# camera-endpoint.net
KiCad netlist of a schematic drawn in EAGLE
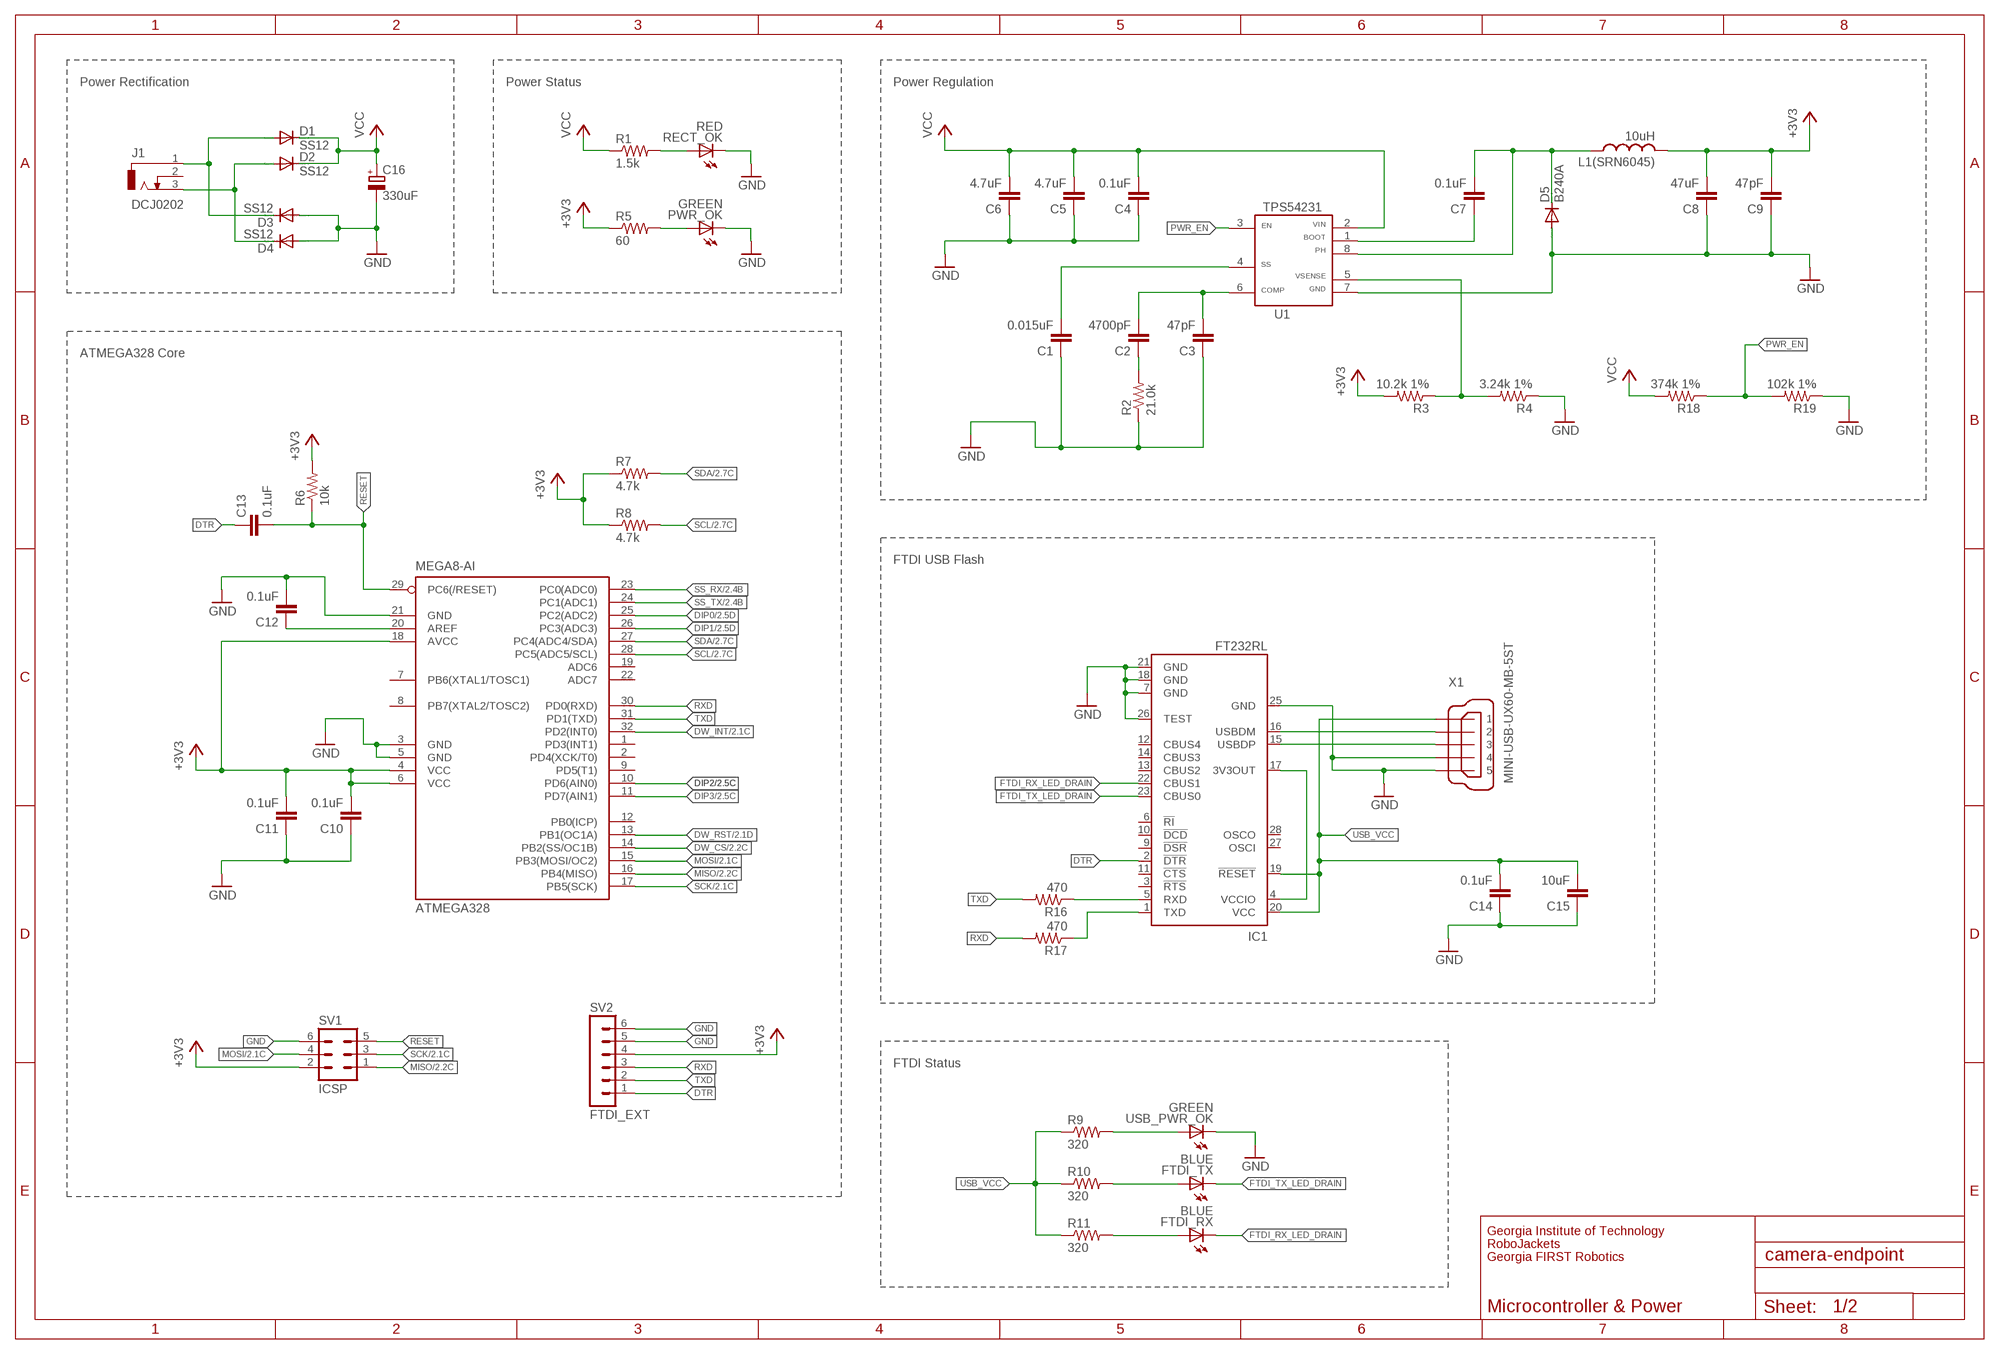
[diagram p0: schematic, sheet 1]
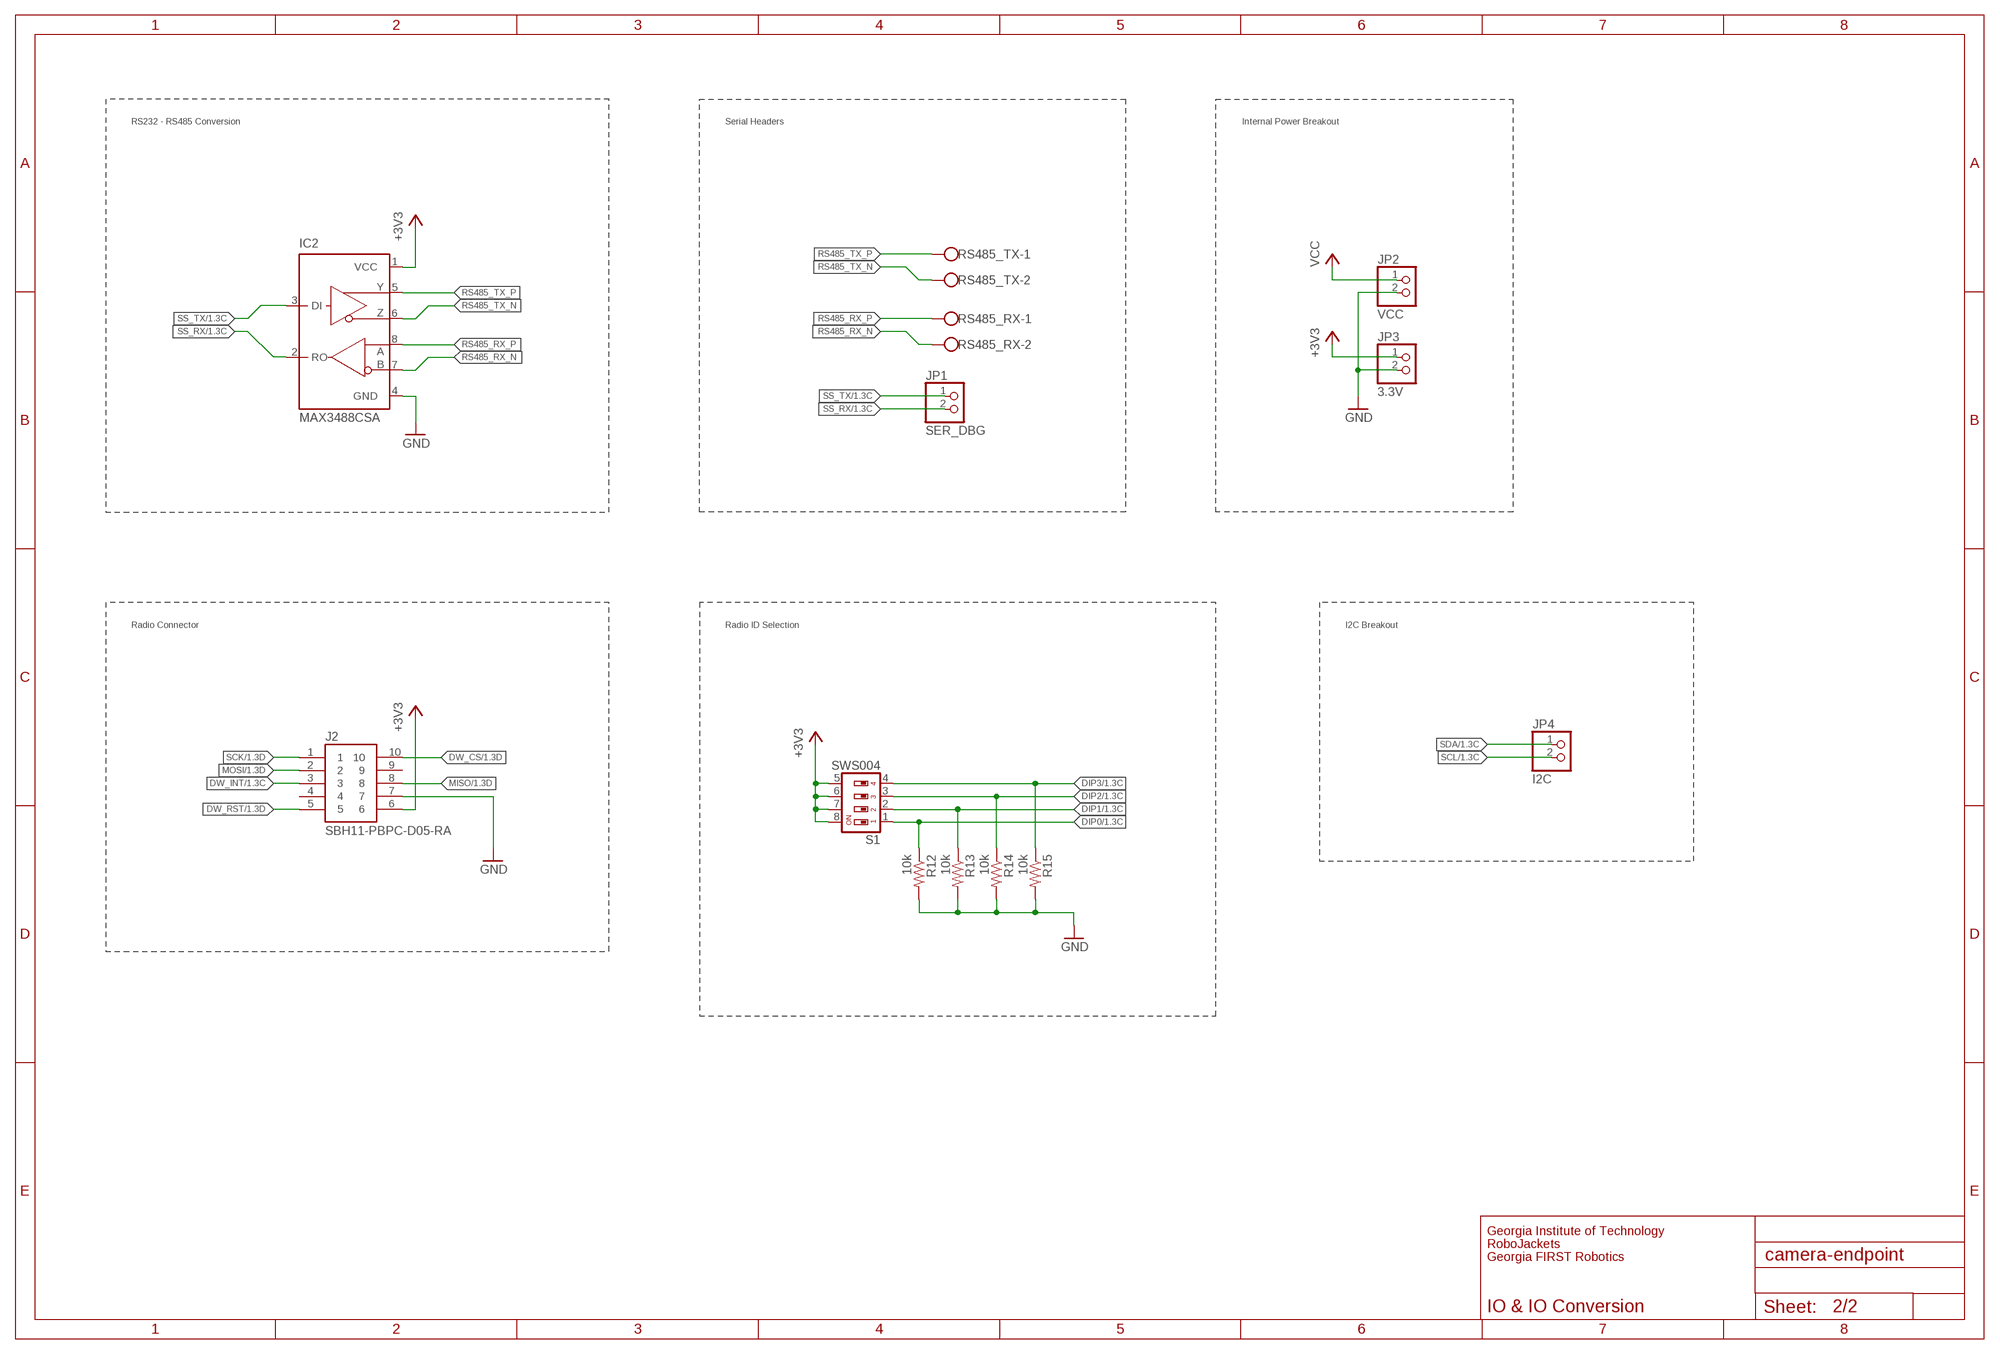
[diagram p1: schematic, sheet 2]

(export (version "E")
  (design (tool "Eeschema 10.0.6"))
  (components
    (comp (ref "IC2")
      (value "MAX3488CSA")
      (footprint "eagle-import:SO08")
      (libsource (lib "eagle-import") (part "MAX3467PAC"))
    )
    (comp (ref "J2")
      (value "SBH11-PBPC-D05-RA")
      (footprint "eagle-import:SBH11-_-D05-RA")
      (fields (field (name "MPN") "SBH11-PBPC-D05-RA-BK"))
      (libsource (lib "eagle-import") (part "SBH11--D05-?RAPBPC"))
    )
    (comp (ref "JP1")
      (value "SER_DBG")
      (footprint "eagle-import:1X02")
      (libsource (lib "eagle-import") (part "PINHD-1X2"))
    )
    (comp (ref "JP2")
      (value "VCC")
      (footprint "eagle-import:1X02")
      (libsource (lib "eagle-import") (part "PINHD-1X2"))
    )
    (comp (ref "JP3")
      (value "3.3V")
      (footprint "eagle-import:1X02")
      (libsource (lib "eagle-import") (part "PINHD-1X2"))
    )
    (comp (ref "JP4")
      (value "I2C")
      (footprint "eagle-import:1X02")
      (libsource (lib "eagle-import") (part "PINHD-1X2"))
    )
    (comp (ref "R12")
      (value "10k")
      (footprint "eagle-import:R0603")
      (libsource (lib "eagle-import") (part "R-US_R0603"))
    )
    (comp (ref "R13")
      (value "10k")
      (footprint "eagle-import:R0603")
      (libsource (lib "eagle-import") (part "R-US_R0603"))
    )
    (comp (ref "R14")
      (value "10k")
      (footprint "eagle-import:R0603")
      (libsource (lib "eagle-import") (part "R-US_R0603"))
    )
    (comp (ref "R15")
      (value "10k")
      (footprint "eagle-import:R0603")
      (libsource (lib "eagle-import") (part "R-US_R0603"))
    )
    (comp (ref "RS485_RX")
      (value "W237-102")
      (footprint "eagle-import:W237-102")
      (fields (field (name "MPN") "237-102"))
      (libsource (lib "eagle-import") (part "W237-102"))
    )
    (comp (ref "RS485_TX")
      (value "W237-102")
      (footprint "eagle-import:W237-102")
      (fields (field (name "MPN") "237-102"))
      (libsource (lib "eagle-import") (part "W237-102"))
    )
    (comp (ref "S1")
      (value "SWS004")
      (footprint "eagle-import:SMS-004")
      (libsource (lib "eagle-import") (part "SWS004"))
    )
    (comp (ref "ATMEGA328")
      (value "MEGA8-AI")
      (footprint "eagle-import:TQFP32-08")
      (fields (field (name "MPN") "ATMEGA8-16AU"))
      (libsource (lib "eagle-import") (part "MEGA8-AI"))
    )
    (comp (ref "C1")
      (value "0.015uF")
      (footprint "eagle-import:C0603")
      (libsource (lib "eagle-import") (part "resistor_348_C-EUC0603"))
    )
    (comp (ref "C2")
      (value "4700pF")
      (footprint "eagle-import:C0603")
      (libsource (lib "eagle-import") (part "resistor_348_C-EUC0603"))
    )
    (comp (ref "C3")
      (value "47pF")
      (footprint "eagle-import:C0603")
      (libsource (lib "eagle-import") (part "resistor_348_C-EUC0603"))
    )
    (comp (ref "C4")
      (value "0.1uF")
      (footprint "eagle-import:C0603")
      (libsource (lib "eagle-import") (part "resistor_348_C-EUC0603"))
    )
    (comp (ref "C5")
      (value "4.7uF")
      (footprint "eagle-import:C0603")
      (libsource (lib "eagle-import") (part "resistor_348_C-EUC0603"))
    )
    (comp (ref "C6")
      (value "4.7uF")
      (footprint "eagle-import:C0603")
      (libsource (lib "eagle-import") (part "resistor_348_C-EUC0603"))
    )
    (comp (ref "C7")
      (value "0.1uF")
      (footprint "eagle-import:C0603")
      (libsource (lib "eagle-import") (part "resistor_348_C-EUC0603"))
    )
    (comp (ref "C8")
      (value "47uF")
      (footprint "eagle-import:C1206")
      (libsource (lib "eagle-import") (part "C-EUC1206"))
    )
    (comp (ref "C9")
      (value "47pF")
      (footprint "eagle-import:C0603")
      (libsource (lib "eagle-import") (part "resistor_348_C-EUC0603"))
    )
    (comp (ref "C10")
      (value "0.1uF")
      (footprint "eagle-import:C0603")
      (libsource (lib "eagle-import") (part "resistor_348_C-EUC0603"))
    )
    (comp (ref "C11")
      (value "0.1uF")
      (footprint "eagle-import:C0603")
      (libsource (lib "eagle-import") (part "resistor_348_C-EUC0603"))
    )
    (comp (ref "C12")
      (value "0.1uF")
      (footprint "eagle-import:C0603")
      (libsource (lib "eagle-import") (part "resistor_348_C-EUC0603"))
    )
    (comp (ref "C13")
      (value "0.1uF")
      (footprint "eagle-import:C0603")
      (libsource (lib "eagle-import") (part "resistor_348_C-EUC0603"))
    )
    (comp (ref "C14")
      (value "0.1uF")
      (footprint "eagle-import:C0603")
      (libsource (lib "eagle-import") (part "resistor_348_C-EUC0603"))
    )
    (comp (ref "C15")
      (value "10uF")
      (footprint "eagle-import:C0603")
      (libsource (lib "eagle-import") (part "resistor_348_C-EUC0603"))
    )
    (comp (ref "C16")
      (value "330uF")
      (footprint "eagle-import:E5-8,5")
      (libsource (lib "eagle-import") (part "CPOL-EUE5-8.5"))
    )
    (comp (ref "D1")
      (value "SS12")
      (footprint "eagle-import:DO214AC")
      (libsource (lib "eagle-import") (part "DIODE-DO214AC"))
    )
    (comp (ref "D2")
      (value "SS12")
      (footprint "eagle-import:DO214AC")
      (libsource (lib "eagle-import") (part "DIODE-DO214AC"))
    )
    (comp (ref "D3")
      (value "SS12")
      (footprint "eagle-import:DO214AC")
      (libsource (lib "eagle-import") (part "DIODE-DO214AC"))
    )
    (comp (ref "D4")
      (value "SS12")
      (footprint "eagle-import:DO214AC")
      (libsource (lib "eagle-import") (part "DIODE-DO214AC"))
    )
    (comp (ref "D5")
      (value "B240A")
      (footprint "eagle-import:DO-214AC")
      (libsource (lib "eagle-import") (part "DIODE-DO-214AC"))
    )
    (comp (ref "FTDI_RX")
      (value "BLUE")
      (footprint "eagle-import:CHIP-LED0603")
      (libsource (lib "eagle-import") (part "LEDCHIP-LED0603"))
    )
    (comp (ref "FTDI_TX")
      (value "BLUE")
      (footprint "eagle-import:CHIP-LED0603")
      (libsource (lib "eagle-import") (part "LEDCHIP-LED0603"))
    )
    (comp (ref "IC1")
      (value "FT232RL")
      (footprint "eagle-import:SSOP28")
      (libsource (lib "eagle-import") (part "FT232RL"))
    )
    (comp (ref "J1")
      (value "DCJ0202")
      (footprint "eagle-import:DCJ0202")
      (libsource (lib "eagle-import") (part "DCJ0202"))
    )
    (comp (ref "L1(SRN6045)")
      (value "10uH")
      (footprint "eagle-import:POWER-CHOKE_WE-TPC")
      (libsource (lib "eagle-import") (part "L-USWE-TPC"))
    )
    (comp (ref "PWR_OK")
      (value "GREEN")
      (footprint "eagle-import:LED5MM")
      (libsource (lib "eagle-import") (part "LED5MM"))
    )
    (comp (ref "R1")
      (value "1.5k")
      (footprint "eagle-import:R0603")
      (libsource (lib "eagle-import") (part "R-US_R0603"))
    )
    (comp (ref "R2")
      (value "21.0k")
      (footprint "eagle-import:R0603")
      (libsource (lib "eagle-import") (part "R-US_R0603"))
    )
    (comp (ref "R3")
      (value "10.2k 1%")
      (footprint "eagle-import:R0603")
      (libsource (lib "eagle-import") (part "R-US_R0603"))
    )
    (comp (ref "R4")
      (value "3.24k 1%")
      (footprint "eagle-import:R0603")
      (libsource (lib "eagle-import") (part "R-US_R0603"))
    )
    (comp (ref "R5")
      (value "60")
      (footprint "eagle-import:R0603")
      (libsource (lib "eagle-import") (part "R-US_R0603"))
    )
    (comp (ref "R6")
      (value "10k")
      (footprint "eagle-import:R0603")
      (libsource (lib "eagle-import") (part "R-US_R0603"))
    )
    (comp (ref "R7")
      (value "4.7k")
      (footprint "eagle-import:R0603")
      (libsource (lib "eagle-import") (part "R-US_R0603"))
    )
    (comp (ref "R8")
      (value "4.7k")
      (footprint "eagle-import:R0603")
      (libsource (lib "eagle-import") (part "R-US_R0603"))
    )
    (comp (ref "R9")
      (value "320")
      (footprint "eagle-import:R0603")
      (libsource (lib "eagle-import") (part "R-US_R0603"))
    )
    (comp (ref "R10")
      (value "320")
      (footprint "eagle-import:R0603")
      (libsource (lib "eagle-import") (part "R-US_R0603"))
    )
    (comp (ref "R11")
      (value "320")
      (footprint "eagle-import:R0603")
      (libsource (lib "eagle-import") (part "R-US_R0603"))
    )
    (comp (ref "R16")
      (value "470")
      (footprint "eagle-import:R0603")
      (libsource (lib "eagle-import") (part "R-US_R0603"))
    )
    (comp (ref "R17")
      (value "470")
      (footprint "eagle-import:R0603")
      (libsource (lib "eagle-import") (part "R-US_R0603"))
    )
    (comp (ref "R18")
      (value "374k 1%")
      (footprint "eagle-import:R0603")
      (libsource (lib "eagle-import") (part "R-US_R0603"))
    )
    (comp (ref "R19")
      (value "102k 1%")
      (footprint "eagle-import:R0603")
      (libsource (lib "eagle-import") (part "R-US_R0603"))
    )
    (comp (ref "RECT_OK")
      (value "RED")
      (footprint "eagle-import:LED5MM")
      (libsource (lib "eagle-import") (part "LED5MM"))
    )
    (comp (ref "SV1")
      (value "ICSP")
      (footprint "eagle-import:MA03-2")
      (libsource (lib "eagle-import") (part "MA03-2"))
    )
    (comp (ref "SV2")
      (value "FTDI_EXT")
      (footprint "eagle-import:MA06-1")
      (libsource (lib "eagle-import") (part "MA06-1"))
    )
    (comp (ref "U1")
      (value "TPS54231SO8")
      (footprint "eagle-import:SO8")
      (libsource (lib "eagle-import") (part "TPS54231SO8"))
    )
    (comp (ref "USB_PWR_OK")
      (value "GREEN")
      (footprint "eagle-import:CHIP-LED0603")
      (libsource (lib "eagle-import") (part "LEDCHIP-LED0603"))
    )
    (comp (ref "X1")
      (value "MINI-USB-UX60-MB-5ST")
      (footprint "eagle-import:UX60-MB-5ST")
      (libsource (lib "eagle-import") (part "MINI-USB-UX60-MB-5ST"))
    )
  )
  (nets
    (net (code "1") (name "+3V3") (class "Default")
      (node (ref "ATMEGA328") (pin "18") (pinfunction "AVCC_18") (pintype "power_in"))
      (node (ref "ATMEGA328") (pin "4") (pinfunction "VCC_4") (pintype "power_in"))
      (node (ref "ATMEGA328") (pin "6") (pinfunction "VCC_6") (pintype "power_in"))
      (node (ref "C10") (pin "2") (pinfunction "2_2") (pintype "passive"))
      (node (ref "C11") (pin "2") (pinfunction "2_2") (pintype "passive"))
      (node (ref "C8") (pin "2") (pinfunction "2_2") (pintype "passive"))
      (node (ref "C9") (pin "2") (pinfunction "2_2") (pintype "passive"))
      (node (ref "IC2") (pin "1") (pinfunction "VCC_1") (pintype "power_in"))
      (node (ref "J2") (pin "6") (pinfunction "6_6") (pintype "bidirectional"))
      (node (ref "JP3") (pin "1") (pinfunction "1_1") (pintype "passive"))
      (node (ref "L1(SRN6045)") (pin "2") (pinfunction "2_2") (pintype "passive"))
      (node (ref "R3") (pin "2") (pinfunction "2_2") (pintype "passive"))
      (node (ref "R5") (pin "1") (pinfunction "1_1") (pintype "passive"))
      (node (ref "R6") (pin "2") (pinfunction "2_2") (pintype "passive"))
      (node (ref "R7") (pin "1") (pinfunction "1_1") (pintype "passive"))
      (node (ref "R8") (pin "1") (pinfunction "1_1") (pintype "passive"))
      (node (ref "S1") (pin "5") (pinfunction "5_5") (pintype "passive"))
      (node (ref "S1") (pin "6") (pinfunction "6_6") (pintype "passive"))
      (node (ref "S1") (pin "7") (pinfunction "7_7") (pintype "passive"))
      (node (ref "S1") (pin "8") (pinfunction "8_8") (pintype "passive"))
      (node (ref "SV1") (pin "2") (pinfunction "2_2") (pintype "passive"))
      (node (ref "SV2") (pin "4") (pinfunction "4_4") (pintype "passive"))
    )
    (net (code "2") (name "DIP0") (class "Default")
      (node (ref "ATMEGA328") (pin "25") (pinfunction "PC2(ADC2)_25") (pintype "bidirectional"))
      (node (ref "R12") (pin "1") (pinfunction "1_1") (pintype "passive"))
      (node (ref "S1") (pin "1") (pinfunction "1_1") (pintype "passive"))
    )
    (net (code "3") (name "DIP1") (class "Default")
      (node (ref "ATMEGA328") (pin "26") (pinfunction "PC3(ADC3)_26") (pintype "bidirectional"))
      (node (ref "R13") (pin "1") (pinfunction "1_1") (pintype "passive"))
      (node (ref "S1") (pin "2") (pinfunction "2_2") (pintype "passive"))
    )
    (net (code "4") (name "DIP2") (class "Default")
      (node (ref "ATMEGA328") (pin "10") (pinfunction "PD6(AIN0)_10") (pintype "bidirectional"))
      (node (ref "R14") (pin "1") (pinfunction "1_1") (pintype "passive"))
      (node (ref "S1") (pin "3") (pinfunction "3_3") (pintype "passive"))
    )
    (net (code "5") (name "DIP3") (class "Default")
      (node (ref "ATMEGA328") (pin "11") (pinfunction "PD7(AIN1)_11") (pintype "bidirectional"))
      (node (ref "R15") (pin "1") (pinfunction "1_1") (pintype "passive"))
      (node (ref "S1") (pin "4") (pinfunction "4_4") (pintype "passive"))
    )
    (net (code "6") (name "DTR") (class "Default")
      (node (ref "C13") (pin "1") (pinfunction "1_1") (pintype "passive"))
      (node (ref "IC1") (pin "2") (pinfunction "~{DTR}_2") (pintype "output"))
      (node (ref "SV2") (pin "1") (pinfunction "1_1") (pintype "passive"))
    )
    (net (code "7") (name "DW_CS") (class "Default")
      (node (ref "ATMEGA328") (pin "14") (pinfunction "PB2(SS/OC1B)_14") (pintype "bidirectional"))
      (node (ref "J2") (pin "10") (pinfunction "10_10") (pintype "bidirectional"))
    )
    (net (code "8") (name "DW_INT") (class "Default")
      (node (ref "ATMEGA328") (pin "32") (pinfunction "PD2(INT0)_32") (pintype "bidirectional"))
      (node (ref "J2") (pin "3") (pinfunction "3_3") (pintype "bidirectional"))
    )
    (net (code "9") (name "DW_RST") (class "Default")
      (node (ref "ATMEGA328") (pin "13") (pinfunction "PB1(OC1A)_13") (pintype "bidirectional"))
      (node (ref "J2") (pin "5") (pinfunction "5_5") (pintype "bidirectional"))
    )
    (net (code "10") (name "FTDI_RX_LED_DRAIN") (class "Default")
      (node (ref "FTDI_RX") (pin "C") (pinfunction "C_C") (pintype "passive"))
      (node (ref "IC1") (pin "22") (pinfunction "CBUS1_22") (pintype "bidirectional"))
    )
    (net (code "11") (name "FTDI_TX_LED_DRAIN") (class "Default")
      (node (ref "FTDI_TX") (pin "C") (pinfunction "C_C") (pintype "passive"))
      (node (ref "IC1") (pin "23") (pinfunction "CBUS0_23") (pintype "bidirectional"))
    )
    (net (code "12") (name "GND") (class "Default")
      (node (ref "ATMEGA328") (pin "21") (pinfunction "GND_21") (pintype "power_in"))
      (node (ref "ATMEGA328") (pin "3") (pinfunction "GND_3") (pintype "power_in"))
      (node (ref "ATMEGA328") (pin "5") (pinfunction "GND_5") (pintype "power_in"))
      (node (ref "C1") (pin "1") (pinfunction "1_1") (pintype "passive"))
      (node (ref "C10") (pin "1") (pinfunction "1_1") (pintype "passive"))
      (node (ref "C11") (pin "1") (pinfunction "1_1") (pintype "passive"))
      (node (ref "C12") (pin "2") (pinfunction "2_2") (pintype "passive"))
      (node (ref "C14") (pin "1") (pinfunction "1_1") (pintype "passive"))
      (node (ref "C15") (pin "1") (pinfunction "1_1") (pintype "passive"))
      (node (ref "C16") (pin "-") (pinfunction "-_-") (pintype "passive"))
      (node (ref "C3") (pin "1") (pinfunction "1_1") (pintype "passive"))
      (node (ref "C4") (pin "1") (pinfunction "1_1") (pintype "passive"))
      (node (ref "C5") (pin "1") (pinfunction "1_1") (pintype "passive"))
      (node (ref "C6") (pin "1") (pinfunction "1_1") (pintype "passive"))
      (node (ref "C8") (pin "1") (pinfunction "1_1") (pintype "passive"))
      (node (ref "C9") (pin "1") (pinfunction "1_1") (pintype "passive"))
      (node (ref "D3") (pin "A") (pinfunction "A_A") (pintype "passive"))
      (node (ref "D4") (pin "A") (pinfunction "A_A") (pintype "passive"))
      (node (ref "D5") (pin "A") (pinfunction "A_A") (pintype "passive"))
      (node (ref "IC1") (pin "18") (pinfunction "GND_18") (pintype "power_in"))
      (node (ref "IC1") (pin "21") (pinfunction "GND_21") (pintype "power_in"))
      (node (ref "IC1") (pin "25") (pinfunction "GND_25") (pintype "power_in"))
      (node (ref "IC1") (pin "26") (pinfunction "TEST_26") (pintype "input"))
      (node (ref "IC1") (pin "7") (pinfunction "GND_7") (pintype "power_in"))
      (node (ref "IC2") (pin "4") (pinfunction "GND_4") (pintype "power_in"))
      (node (ref "J2") (pin "7") (pinfunction "7_7") (pintype "bidirectional"))
      (node (ref "JP2") (pin "2") (pinfunction "2_2") (pintype "passive"))
      (node (ref "JP3") (pin "2") (pinfunction "2_2") (pintype "passive"))
      (node (ref "PWR_OK") (pin "K") (pinfunction "C_K") (pintype "passive"))
      (node (ref "R12") (pin "2") (pinfunction "2_2") (pintype "passive"))
      (node (ref "R13") (pin "2") (pinfunction "2_2") (pintype "passive"))
      (node (ref "R14") (pin "2") (pinfunction "2_2") (pintype "passive"))
      (node (ref "R15") (pin "2") (pinfunction "2_2") (pintype "passive"))
      (node (ref "R19") (pin "1") (pinfunction "1_1") (pintype "passive"))
      (node (ref "R2") (pin "1") (pinfunction "1_1") (pintype "passive"))
      (node (ref "R4") (pin "1") (pinfunction "1_1") (pintype "passive"))
      (node (ref "RECT_OK") (pin "K") (pinfunction "C_K") (pintype "passive"))
      (node (ref "SV1") (pin "6") (pinfunction "6_6") (pintype "passive"))
      (node (ref "SV2") (pin "5") (pinfunction "5_5") (pintype "passive"))
      (node (ref "SV2") (pin "6") (pinfunction "6_6") (pintype "passive"))
      (node (ref "U1") (pin "7") (pinfunction "7_7") (pintype "bidirectional"))
      (node (ref "USB_PWR_OK") (pin "C") (pinfunction "C_C") (pintype "passive"))
      (node (ref "X1") (pin "4") (pinfunction "4_4") (pintype "input"))
      (node (ref "X1") (pin "5") (pinfunction "5_5") (pintype "input"))
    )
    (net (code "13") (name "MISO") (class "Default")
      (node (ref "ATMEGA328") (pin "16") (pinfunction "PB4(MISO)_16") (pintype "bidirectional"))
      (node (ref "J2") (pin "8") (pinfunction "8_8") (pintype "bidirectional"))
      (node (ref "SV1") (pin "1") (pinfunction "1_1") (pintype "passive"))
    )
    (net (code "14") (name "MOSI") (class "Default")
      (node (ref "ATMEGA328") (pin "15") (pinfunction "PB3(MOSI/OC2)_15") (pintype "bidirectional"))
      (node (ref "J2") (pin "2") (pinfunction "2_2") (pintype "bidirectional"))
      (node (ref "SV1") (pin "4") (pinfunction "4_4") (pintype "passive"))
    )
    (net (code "15") (name "Net-(ATMEGA328-AREF)") (class "Default")
      (node (ref "ATMEGA328") (pin "20") (pinfunction "AREF_20") (pintype "passive"))
      (node (ref "C12") (pin "1") (pinfunction "1_1") (pintype "passive"))
    )
    (net (code "16") (name "Net-(C1-Pad2)") (class "Default")
      (node (ref "C1") (pin "2") (pinfunction "2_2") (pintype "passive"))
      (node (ref "U1") (pin "4") (pinfunction "4_4") (pintype "bidirectional"))
    )
    (net (code "17") (name "Net-(C2-Pad1)") (class "Default")
      (node (ref "C2") (pin "1") (pinfunction "1_1") (pintype "passive"))
      (node (ref "R2") (pin "2") (pinfunction "2_2") (pintype "passive"))
    )
    (net (code "18") (name "Net-(C2-Pad2)") (class "Default")
      (node (ref "C2") (pin "2") (pinfunction "2_2") (pintype "passive"))
      (node (ref "C3") (pin "2") (pinfunction "2_2") (pintype "passive"))
      (node (ref "U1") (pin "6") (pinfunction "6_6") (pintype "bidirectional"))
    )
    (net (code "19") (name "Net-(C7-Pad1)") (class "Default")
      (node (ref "C7") (pin "1") (pinfunction "1_1") (pintype "passive"))
      (node (ref "U1") (pin "1") (pinfunction "1_1") (pintype "bidirectional"))
    )
    (net (code "20") (name "Net-(C7-Pad2)") (class "Default")
      (node (ref "C7") (pin "2") (pinfunction "2_2") (pintype "passive"))
      (node (ref "D5") (pin "C") (pinfunction "C_C") (pintype "passive"))
      (node (ref "L1(SRN6045)") (pin "1") (pinfunction "1_1") (pintype "passive"))
      (node (ref "U1") (pin "8") (pinfunction "8_8") (pintype "bidirectional"))
    )
    (net (code "21") (name "Net-(D1-PadA)") (class "Default")
      (node (ref "D1") (pin "A") (pinfunction "A_A") (pintype "passive"))
      (node (ref "D3") (pin "C") (pinfunction "C_C") (pintype "passive"))
      (node (ref "J1") (pin "1") (pinfunction "1_1") (pintype "passive"))
    )
    (net (code "22") (name "Net-(D2-PadA)") (class "Default")
      (node (ref "D2") (pin "A") (pinfunction "A_A") (pintype "passive"))
      (node (ref "D4") (pin "C") (pinfunction "C_C") (pintype "passive"))
      (node (ref "J1") (pin "3") (pinfunction "3_3") (pintype "passive"))
    )
    (net (code "23") (name "Net-(FTDI_RX-PadA)") (class "Default")
      (node (ref "FTDI_RX") (pin "A") (pinfunction "A_A") (pintype "passive"))
      (node (ref "R11") (pin "2") (pinfunction "2_2") (pintype "passive"))
    )
    (net (code "24") (name "Net-(FTDI_TX-PadA)") (class "Default")
      (node (ref "FTDI_TX") (pin "A") (pinfunction "A_A") (pintype "passive"))
      (node (ref "R10") (pin "2") (pinfunction "2_2") (pintype "passive"))
    )
    (net (code "25") (name "Net-(IC1-3V3OUT)") (class "Default")
      (node (ref "IC1") (pin "17") (pinfunction "3V3OUT_17") (pintype "output"))
      (node (ref "IC1") (pin "4") (pinfunction "VCCIO_4") (pintype "power_in"))
    )
    (net (code "26") (name "Net-(IC1-RXD)") (class "Default")
      (node (ref "IC1") (pin "5") (pinfunction "RXD_5") (pintype "input"))
      (node (ref "R16") (pin "1") (pinfunction "1_1") (pintype "passive"))
    )
    (net (code "27") (name "Net-(IC1-TXD)") (class "Default")
      (node (ref "IC1") (pin "1") (pinfunction "TXD_1") (pintype "output"))
      (node (ref "R17") (pin "1") (pinfunction "1_1") (pintype "passive"))
    )
    (net (code "28") (name "Net-(IC1-USBDM)") (class "Default")
      (node (ref "IC1") (pin "16") (pinfunction "USBDM_16") (pintype "bidirectional"))
      (node (ref "X1") (pin "2") (pinfunction "2_2") (pintype "input"))
    )
    (net (code "29") (name "Net-(IC1-USBDP)") (class "Default")
      (node (ref "IC1") (pin "15") (pinfunction "USBDP_15") (pintype "bidirectional"))
      (node (ref "X1") (pin "3") (pinfunction "3_3") (pintype "input"))
    )
    (net (code "30") (name "Net-(PWR_OK-PadA)") (class "Default")
      (node (ref "PWR_OK") (pin "A") (pinfunction "A_A") (pintype "passive"))
      (node (ref "R5") (pin "2") (pinfunction "2_2") (pintype "passive"))
    )
    (net (code "31") (name "Net-(R1-Pad2)") (class "Default")
      (node (ref "R1") (pin "2") (pinfunction "2_2") (pintype "passive"))
      (node (ref "RECT_OK") (pin "A") (pinfunction "A_A") (pintype "passive"))
    )
    (net (code "32") (name "Net-(R3-Pad1)") (class "Default")
      (node (ref "R3") (pin "1") (pinfunction "1_1") (pintype "passive"))
      (node (ref "R4") (pin "2") (pinfunction "2_2") (pintype "passive"))
      (node (ref "U1") (pin "5") (pinfunction "5_5") (pintype "bidirectional"))
    )
    (net (code "33") (name "Net-(R9-Pad2)") (class "Default")
      (node (ref "R9") (pin "2") (pinfunction "2_2") (pintype "passive"))
      (node (ref "USB_PWR_OK") (pin "A") (pinfunction "A_A") (pintype "passive"))
    )
    (net (code "34") (name "PWR_EN") (class "Default")
      (node (ref "R18") (pin "1") (pinfunction "1_1") (pintype "passive"))
      (node (ref "R19") (pin "2") (pinfunction "2_2") (pintype "passive"))
      (node (ref "U1") (pin "3") (pinfunction "3_3") (pintype "bidirectional"))
    )
    (net (code "35") (name "RESET") (class "Default")
      (node (ref "ATMEGA328") (pin "29") (pinfunction "PC6(/RESET)_29") (pintype "bidirectional"))
      (node (ref "C13") (pin "2") (pinfunction "2_2") (pintype "passive"))
      (node (ref "R6") (pin "1") (pinfunction "1_1") (pintype "passive"))
      (node (ref "SV1") (pin "5") (pinfunction "5_5") (pintype "passive"))
    )
    (net (code "36") (name "RS485_RX_N") (class "Default")
      (node (ref "IC2") (pin "7") (pinfunction "B_7") (pintype "passive"))
      (node (ref "RS485_RX") (pin "2") (pinfunction "KL_2") (pintype "passive"))
    )
    (net (code "37") (name "RS485_RX_P") (class "Default")
      (node (ref "IC2") (pin "8") (pinfunction "A_8") (pintype "passive"))
      (node (ref "RS485_RX") (pin "1") (pinfunction "KL_1") (pintype "passive"))
    )
    (net (code "38") (name "RS485_TX_N") (class "Default")
      (node (ref "IC2") (pin "6") (pinfunction "Z_6") (pintype "passive"))
      (node (ref "RS485_TX") (pin "2") (pinfunction "KL_2") (pintype "passive"))
    )
    (net (code "39") (name "RS485_TX_P") (class "Default")
      (node (ref "IC2") (pin "5") (pinfunction "Y_5") (pintype "passive"))
      (node (ref "RS485_TX") (pin "1") (pinfunction "KL_1") (pintype "passive"))
    )
    (net (code "40") (name "RXD") (class "Default")
      (node (ref "ATMEGA328") (pin "30") (pinfunction "PD0(RXD)_30") (pintype "bidirectional"))
      (node (ref "R17") (pin "2") (pinfunction "2_2") (pintype "passive"))
      (node (ref "SV2") (pin "3") (pinfunction "3_3") (pintype "passive"))
    )
    (net (code "41") (name "SCK") (class "Default")
      (node (ref "ATMEGA328") (pin "17") (pinfunction "PB5(SCK)_17") (pintype "bidirectional"))
      (node (ref "J2") (pin "1") (pinfunction "1_1") (pintype "bidirectional"))
      (node (ref "SV1") (pin "3") (pinfunction "3_3") (pintype "passive"))
    )
    (net (code "42") (name "SCL") (class "Default")
      (node (ref "ATMEGA328") (pin "28") (pinfunction "PC5(ADC5/SCL)_28") (pintype "bidirectional"))
      (node (ref "JP4") (pin "2") (pinfunction "2_2") (pintype "passive"))
      (node (ref "R8") (pin "2") (pinfunction "2_2") (pintype "passive"))
    )
    (net (code "43") (name "SDA") (class "Default")
      (node (ref "ATMEGA328") (pin "27") (pinfunction "PC4(ADC4/SDA)_27") (pintype "bidirectional"))
      (node (ref "JP4") (pin "1") (pinfunction "1_1") (pintype "passive"))
      (node (ref "R7") (pin "2") (pinfunction "2_2") (pintype "passive"))
    )
    (net (code "44") (name "SS_RX") (class "Default")
      (node (ref "ATMEGA328") (pin "23") (pinfunction "PC0(ADC0)_23") (pintype "bidirectional"))
      (node (ref "IC2") (pin "2") (pinfunction "RO_2") (pintype "output"))
      (node (ref "JP1") (pin "2") (pinfunction "2_2") (pintype "passive"))
    )
    (net (code "45") (name "SS_TX") (class "Default")
      (node (ref "ATMEGA328") (pin "24") (pinfunction "PC1(ADC1)_24") (pintype "bidirectional"))
      (node (ref "IC2") (pin "3") (pinfunction "DI_3") (pintype "input"))
      (node (ref "JP1") (pin "1") (pinfunction "1_1") (pintype "passive"))
    )
    (net (code "46") (name "TXD") (class "Default")
      (node (ref "ATMEGA328") (pin "31") (pinfunction "PD1(TXD)_31") (pintype "bidirectional"))
      (node (ref "R16") (pin "2") (pinfunction "2_2") (pintype "passive"))
      (node (ref "SV2") (pin "2") (pinfunction "2_2") (pintype "passive"))
    )
    (net (code "47") (name "USB_VCC") (class "Default")
      (node (ref "C14") (pin "2") (pinfunction "2_2") (pintype "passive"))
      (node (ref "C15") (pin "2") (pinfunction "2_2") (pintype "passive"))
      (node (ref "IC1") (pin "19") (pinfunction "~{RESET}_19") (pintype "input"))
      (node (ref "IC1") (pin "20") (pinfunction "VCC_20") (pintype "power_in"))
      (node (ref "R10") (pin "1") (pinfunction "1_1") (pintype "passive"))
      (node (ref "R11") (pin "1") (pinfunction "1_1") (pintype "passive"))
      (node (ref "R9") (pin "1") (pinfunction "1_1") (pintype "passive"))
      (node (ref "X1") (pin "1") (pinfunction "1_1") (pintype "input"))
    )
    (net (code "48") (name "VCC") (class "Default")
      (node (ref "C16") (pin "+") (pinfunction "+_+") (pintype "passive"))
      (node (ref "C4") (pin "2") (pinfunction "2_2") (pintype "passive"))
      (node (ref "C5") (pin "2") (pinfunction "2_2") (pintype "passive"))
      (node (ref "C6") (pin "2") (pinfunction "2_2") (pintype "passive"))
      (node (ref "D1") (pin "C") (pinfunction "C_C") (pintype "passive"))
      (node (ref "D2") (pin "C") (pinfunction "C_C") (pintype "passive"))
      (node (ref "JP2") (pin "1") (pinfunction "1_1") (pintype "passive"))
      (node (ref "R1") (pin "1") (pinfunction "1_1") (pintype "passive"))
      (node (ref "R18") (pin "2") (pinfunction "2_2") (pintype "passive"))
      (node (ref "U1") (pin "2") (pinfunction "2_2") (pintype "bidirectional"))
    )
    (net (code "49") (name "unconnected-(ATMEGA328-ADC6-Pad19)") (class "Default")
      (node (ref "ATMEGA328") (pin "19") (pinfunction "ADC6_19") (pintype "bidirectional"))
    )
    (net (code "50") (name "unconnected-(ATMEGA328-ADC7-Pad22)") (class "Default")
      (node (ref "ATMEGA328") (pin "22") (pinfunction "ADC7_22") (pintype "bidirectional"))
    )
    (net (code "51") (name "unconnected-(ATMEGA328-PB0(ICP)-Pad12)") (class "Default")
      (node (ref "ATMEGA328") (pin "12") (pinfunction "PB0(ICP)_12") (pintype "bidirectional"))
    )
    (net (code "52") (name "unconnected-(ATMEGA328-PB6(XTAL1{slash}TOSC1)-Pad7)") (class "Default")
      (node (ref "ATMEGA328") (pin "7") (pinfunction "PB6(XTAL1/TOSC1)_7") (pintype "bidirectional"))
    )
    (net (code "53") (name "unconnected-(ATMEGA328-PB7(XTAL2{slash}TOSC2)-Pad8)") (class "Default")
      (node (ref "ATMEGA328") (pin "8") (pinfunction "PB7(XTAL2/TOSC2)_8") (pintype "bidirectional"))
    )
    (net (code "54") (name "unconnected-(ATMEGA328-PD3(INT1)-Pad1)") (class "Default")
      (node (ref "ATMEGA328") (pin "1") (pinfunction "PD3(INT1)_1") (pintype "bidirectional"))
    )
    (net (code "55") (name "unconnected-(ATMEGA328-PD4(XCK{slash}T0)-Pad2)") (class "Default")
      (node (ref "ATMEGA328") (pin "2") (pinfunction "PD4(XCK/T0)_2") (pintype "bidirectional"))
    )
    (net (code "56") (name "unconnected-(ATMEGA328-PD5(T1)-Pad9)") (class "Default")
      (node (ref "ATMEGA328") (pin "9") (pinfunction "PD5(T1)_9") (pintype "bidirectional"))
    )
    (net (code "57") (name "unconnected-(IC1-CBUS2-Pad13)") (class "Default")
      (node (ref "IC1") (pin "13") (pinfunction "CBUS2_13") (pintype "bidirectional"))
    )
    (net (code "58") (name "unconnected-(IC1-CBUS3-Pad14)") (class "Default")
      (node (ref "IC1") (pin "14") (pinfunction "CBUS3_14") (pintype "bidirectional"))
    )
    (net (code "59") (name "unconnected-(IC1-CBUS4-Pad12)") (class "Default")
      (node (ref "IC1") (pin "12") (pinfunction "CBUS4_12") (pintype "bidirectional"))
    )
    (net (code "60") (name "unconnected-(IC1-OSCI-Pad27)") (class "Default")
      (node (ref "IC1") (pin "27") (pinfunction "OSCI_27") (pintype "input"))
    )
    (net (code "61") (name "unconnected-(IC1-OSCO-Pad28)") (class "Default")
      (node (ref "IC1") (pin "28") (pinfunction "OSCO_28") (pintype "output"))
    )
    (net (code "62") (name "unconnected-(IC1-~{CTS}-Pad11)") (class "Default")
      (node (ref "IC1") (pin "11") (pinfunction "~{CTS}_11") (pintype "input"))
    )
    (net (code "63") (name "unconnected-(IC1-~{DCD}-Pad10)") (class "Default")
      (node (ref "IC1") (pin "10") (pinfunction "~{DCD}_10") (pintype "input"))
    )
    (net (code "64") (name "unconnected-(IC1-~{DSR}-Pad9)") (class "Default")
      (node (ref "IC1") (pin "9") (pinfunction "~{DSR}_9") (pintype "input"))
    )
    (net (code "65") (name "unconnected-(IC1-~{RI}-Pad6)") (class "Default")
      (node (ref "IC1") (pin "6") (pinfunction "~{RI}_6") (pintype "input"))
    )
    (net (code "66") (name "unconnected-(IC1-~{RTS}-Pad3)") (class "Default")
      (node (ref "IC1") (pin "3") (pinfunction "~{RTS}_3") (pintype "output"))
    )
    (net (code "67") (name "unconnected-(J1-Pad2)") (class "Default")
      (node (ref "J1") (pin "2") (pinfunction "2_2") (pintype "passive"))
    )
    (net (code "68") (name "unconnected-(J2-Pad4)") (class "Default")
      (node (ref "J2") (pin "4") (pinfunction "4_4") (pintype "bidirectional"))
    )
    (net (code "69") (name "unconnected-(J2-Pad9)") (class "Default")
      (node (ref "J2") (pin "9") (pinfunction "9_9") (pintype "bidirectional"))
    )
  )
)
